# Host.net
KiCad netlist of a schematic drawn in Altium Designer
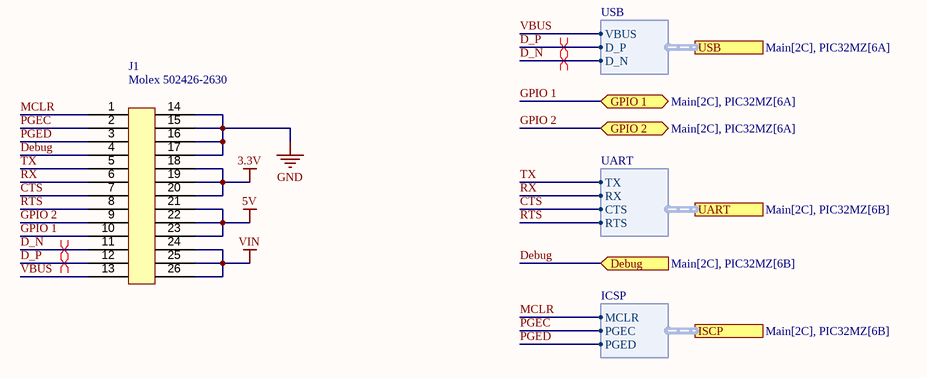
[diagram p0: Host.SchDoc]

(export (version "E")
  (design (tool "Eeschema 10.0.6"))
  (components
    (comp (ref "J1")
      (value "Molex 502426-2630")
      (footprint "Molex 502426-2630")
      (libsource (lib "x-io") (part "Molex 502426-2630"))
    )
  )
  (nets
    (net (code "4") (name "/CTS") (class "Default")
      (node (ref "J1") (pin "7") (pinfunction "7_7") (pintype "passive"))
    )
    (net (code "5") (name "/D_N") (class "Default")
      (node (ref "J1") (pin "11") (pinfunction "11_11") (pintype "passive"))
    )
    (net (code "6") (name "/D_P") (class "Default")
      (node (ref "J1") (pin "12") (pinfunction "12_12") (pintype "passive"))
    )
    (net (code "7") (name "/Debug") (class "Default")
      (node (ref "J1") (pin "4") (pinfunction "4_4") (pintype "passive"))
    )
    (net (code "8") (name "/GPIO 1") (class "Default")
      (node (ref "J1") (pin "10") (pinfunction "10_10") (pintype "passive"))
    )
    (net (code "9") (name "/GPIO 2") (class "Default")
      (node (ref "J1") (pin "9") (pinfunction "9_9") (pintype "passive"))
    )
    (net (code "10") (name "/MCLR") (class "Default")
      (node (ref "J1") (pin "1") (pinfunction "1_1") (pintype "passive"))
    )
    (net (code "11") (name "/PGEC") (class "Default")
      (node (ref "J1") (pin "2") (pinfunction "2_2") (pintype "passive"))
    )
    (net (code "12") (name "/PGED") (class "Default")
      (node (ref "J1") (pin "3") (pinfunction "3_3") (pintype "passive"))
    )
    (net (code "13") (name "/RTS") (class "Default")
      (node (ref "J1") (pin "8") (pinfunction "8_8") (pintype "passive"))
    )
    (net (code "14") (name "/RX") (class "Default")
      (node (ref "J1") (pin "6") (pinfunction "6_6") (pintype "passive"))
    )
    (net (code "15") (name "/TX") (class "Default")
      (node (ref "J1") (pin "5") (pinfunction "5_5") (pintype "passive"))
    )
    (net (code "16") (name "/VBUS") (class "Default")
      (node (ref "J1") (pin "13") (pinfunction "13_13") (pintype "passive"))
    )
    (net (code "20") (name "3.3V") (class "Default")
      (node (ref "J1") (pin "18") (pinfunction "18_18") (pintype "passive"))
      (node (ref "J1") (pin "19") (pinfunction "19_19") (pintype "passive"))
      (node (ref "J1") (pin "20") (pinfunction "20_20") (pintype "passive"))
    )
    (net (code "21") (name "5V") (class "Default")
      (node (ref "J1") (pin "21") (pinfunction "21_21") (pintype "passive"))
      (node (ref "J1") (pin "22") (pinfunction "22_22") (pintype "passive"))
      (node (ref "J1") (pin "23") (pinfunction "23_23") (pintype "passive"))
    )
    (net (code "22") (name "GND") (class "Default")
      (node (ref "J1") (pin "14") (pinfunction "14_14") (pintype "passive"))
      (node (ref "J1") (pin "15") (pinfunction "15_15") (pintype "passive"))
      (node (ref "J1") (pin "16") (pinfunction "16_16") (pintype "passive"))
      (node (ref "J1") (pin "17") (pinfunction "17_17") (pintype "passive"))
    )
    (net (code "23") (name "VIN") (class "Default")
      (node (ref "J1") (pin "24") (pinfunction "24_24") (pintype "passive"))
      (node (ref "J1") (pin "25") (pinfunction "25_25") (pintype "passive"))
      (node (ref "J1") (pin "26") (pinfunction "26_26") (pintype "passive"))
    )
  )
)
